# DriverModuleSkinny.net
KiCad netlist of a schematic drawn in EAGLE
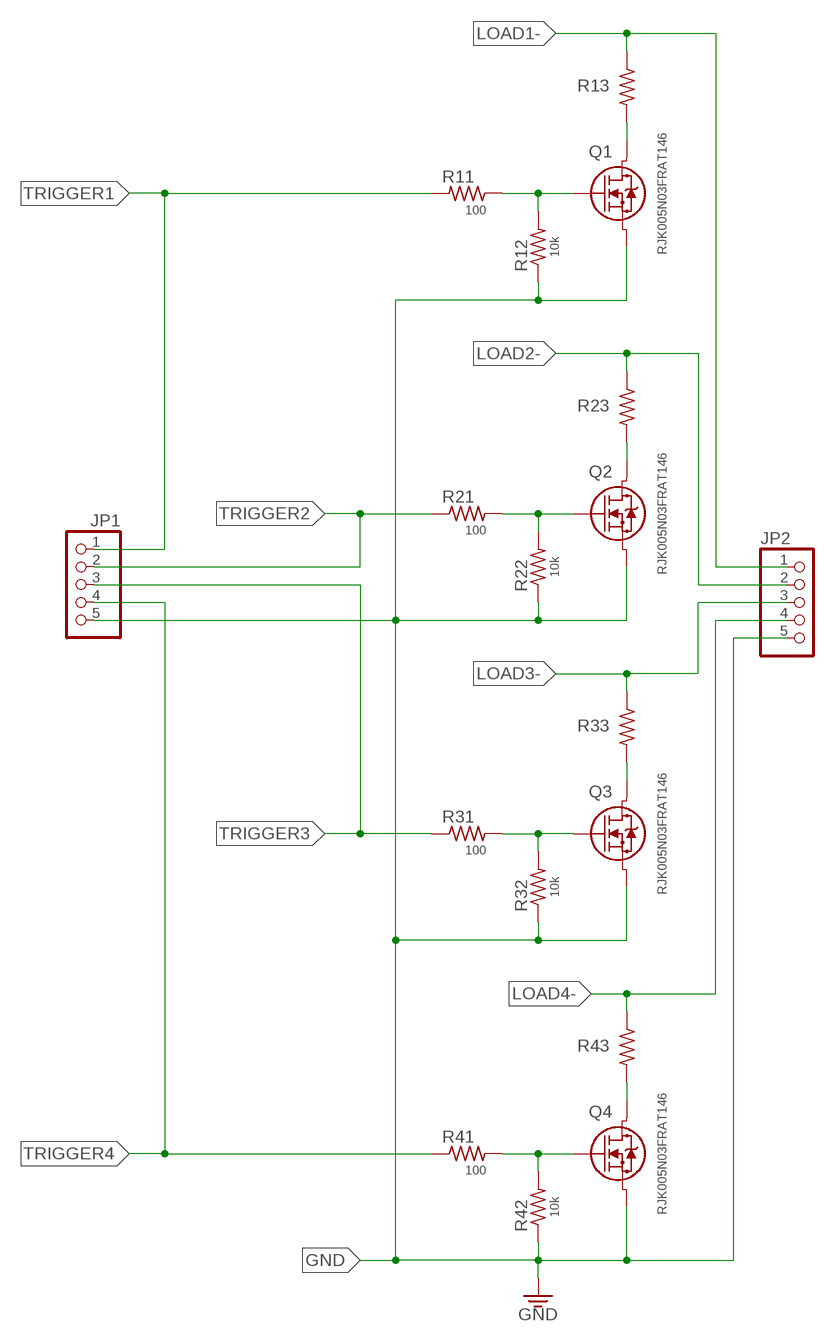
[diagram p0: schematic, sheet 1]

(export (version "E")
  (design (tool "Eeschema 10.0.6"))
  (components
    (comp (ref "JP1")
      (value "HEADER-1X576MIL")
      (footprint "eagle-import:1X05_ROUND_76")
      (libsource (lib "eagle-import") (part "HEADER-1X576MIL"))
    )
    (comp (ref "JP2")
      (value "HEADER-1X576MIL")
      (footprint "eagle-import:1X05_ROUND_76")
      (libsource (lib "eagle-import") (part "HEADER-1X576MIL"))
    )
    (comp (ref "Q1")
      (value "RJK005N03FRAT146")
      (footprint "eagle-import:TRANS_RHK003N_ROM-M")
      (fields (field (name "COPYRIGHT") "Copyright (C) 2022 Ultra Librarian. All rights reserved."))
      (libsource (lib "eagle-import") (part "RJK005N03FRAT146TRANS_RHK003N_ROM-M"))
    )
    (comp (ref "Q2")
      (value "RJK005N03FRAT146")
      (footprint "eagle-import:TRANS_RHK003N_ROM-M")
      (fields (field (name "COPYRIGHT") "Copyright (C) 2022 Ultra Librarian. All rights reserved."))
      (libsource (lib "eagle-import") (part "RJK005N03FRAT146TRANS_RHK003N_ROM-M"))
    )
    (comp (ref "Q3")
      (value "RJK005N03FRAT146")
      (footprint "eagle-import:TRANS_RHK003N_ROM-M")
      (fields (field (name "COPYRIGHT") "Copyright (C) 2022 Ultra Librarian. All rights reserved."))
      (libsource (lib "eagle-import") (part "RJK005N03FRAT146TRANS_RHK003N_ROM-M"))
    )
    (comp (ref "Q4")
      (value "RJK005N03FRAT146")
      (footprint "eagle-import:TRANS_RHK003N_ROM-M")
      (fields (field (name "COPYRIGHT") "Copyright (C) 2022 Ultra Librarian. All rights reserved."))
      (libsource (lib "eagle-import") (part "RJK005N03FRAT146TRANS_RHK003N_ROM-M"))
    )
    (comp (ref "R11")
      (value "100")
      (footprint "eagle-import:R0603")
      (libsource (lib "eagle-import") (part "R-US_R0603"))
    )
    (comp (ref "R12")
      (value "10k")
      (footprint "eagle-import:R0603")
      (libsource (lib "eagle-import") (part "R-US_R0603"))
    )
    (comp (ref "R13")
      (value "R-US_R1206")
      (footprint "eagle-import:R1206")
      (libsource (lib "eagle-import") (part "R-US_R1206"))
    )
    (comp (ref "R21")
      (value "100")
      (footprint "eagle-import:R0603")
      (libsource (lib "eagle-import") (part "R-US_R0603"))
    )
    (comp (ref "R22")
      (value "10k")
      (footprint "eagle-import:R0603")
      (libsource (lib "eagle-import") (part "R-US_R0603"))
    )
    (comp (ref "R23")
      (value "R-US_R1206")
      (footprint "eagle-import:R1206")
      (libsource (lib "eagle-import") (part "R-US_R1206"))
    )
    (comp (ref "R31")
      (value "100")
      (footprint "eagle-import:R0603")
      (libsource (lib "eagle-import") (part "R-US_R0603"))
    )
    (comp (ref "R32")
      (value "10k")
      (footprint "eagle-import:R0603")
      (libsource (lib "eagle-import") (part "R-US_R0603"))
    )
    (comp (ref "R33")
      (value "R-US_R1206")
      (footprint "eagle-import:R1206")
      (libsource (lib "eagle-import") (part "R-US_R1206"))
    )
    (comp (ref "R41")
      (value "100")
      (footprint "eagle-import:R0603")
      (libsource (lib "eagle-import") (part "R-US_R0603"))
    )
    (comp (ref "R42")
      (value "10k")
      (footprint "eagle-import:R0603")
      (libsource (lib "eagle-import") (part "R-US_R0603"))
    )
    (comp (ref "R43")
      (value "R-US_R1206")
      (footprint "eagle-import:R1206")
      (libsource (lib "eagle-import") (part "R-US_R1206"))
    )
  )
  (nets
    (net (code "1") (name "GND") (class "Default")
      (node (ref "JP1") (pin "5") (pinfunction "5_5") (pintype "passive"))
      (node (ref "JP2") (pin "5") (pinfunction "5_5") (pintype "passive"))
      (node (ref "Q1") (pin "3") (pinfunction "3_3") (pintype "passive"))
      (node (ref "Q2") (pin "3") (pinfunction "3_3") (pintype "passive"))
      (node (ref "Q3") (pin "3") (pinfunction "3_3") (pintype "passive"))
      (node (ref "Q4") (pin "3") (pinfunction "3_3") (pintype "passive"))
      (node (ref "R12") (pin "1") (pinfunction "1_1") (pintype "passive"))
      (node (ref "R22") (pin "1") (pinfunction "1_1") (pintype "passive"))
      (node (ref "R32") (pin "1") (pinfunction "1_1") (pintype "passive"))
      (node (ref "R42") (pin "1") (pinfunction "1_1") (pintype "passive"))
    )
    (net (code "2") (name "LOAD1-") (class "Default")
      (node (ref "JP2") (pin "1") (pinfunction "1_1") (pintype "passive"))
      (node (ref "R13") (pin "1") (pinfunction "1_1") (pintype "passive"))
    )
    (net (code "3") (name "LOAD2-") (class "Default")
      (node (ref "JP2") (pin "2") (pinfunction "2_2") (pintype "passive"))
      (node (ref "R23") (pin "1") (pinfunction "1_1") (pintype "passive"))
    )
    (net (code "4") (name "LOAD3-") (class "Default")
      (node (ref "JP2") (pin "3") (pinfunction "3_3") (pintype "passive"))
      (node (ref "R33") (pin "1") (pinfunction "1_1") (pintype "passive"))
    )
    (net (code "5") (name "LOAD4-") (class "Default")
      (node (ref "JP2") (pin "4") (pinfunction "4_4") (pintype "passive"))
      (node (ref "R43") (pin "1") (pinfunction "1_1") (pintype "passive"))
    )
    (net (code "6") (name "Net-(Q1-1)") (class "Default")
      (node (ref "Q1") (pin "2") (pinfunction "1_2") (pintype "passive"))
      (node (ref "R11") (pin "1") (pinfunction "1_1") (pintype "passive"))
      (node (ref "R12") (pin "2") (pinfunction "2_2") (pintype "passive"))
    )
    (net (code "7") (name "Net-(Q1-2)") (class "Default")
      (node (ref "Q1") (pin "1") (pinfunction "2_1") (pintype "passive"))
      (node (ref "R13") (pin "2") (pinfunction "2_2") (pintype "passive"))
    )
    (net (code "8") (name "Net-(Q2-1)") (class "Default")
      (node (ref "Q2") (pin "2") (pinfunction "1_2") (pintype "passive"))
      (node (ref "R21") (pin "2") (pinfunction "2_2") (pintype "passive"))
      (node (ref "R22") (pin "2") (pinfunction "2_2") (pintype "passive"))
    )
    (net (code "9") (name "Net-(Q2-2)") (class "Default")
      (node (ref "Q2") (pin "1") (pinfunction "2_1") (pintype "passive"))
      (node (ref "R23") (pin "2") (pinfunction "2_2") (pintype "passive"))
    )
    (net (code "10") (name "Net-(Q3-1)") (class "Default")
      (node (ref "Q3") (pin "2") (pinfunction "1_2") (pintype "passive"))
      (node (ref "R31") (pin "2") (pinfunction "2_2") (pintype "passive"))
      (node (ref "R32") (pin "2") (pinfunction "2_2") (pintype "passive"))
    )
    (net (code "11") (name "Net-(Q3-2)") (class "Default")
      (node (ref "Q3") (pin "1") (pinfunction "2_1") (pintype "passive"))
      (node (ref "R33") (pin "2") (pinfunction "2_2") (pintype "passive"))
    )
    (net (code "12") (name "Net-(Q4-1)") (class "Default")
      (node (ref "Q4") (pin "2") (pinfunction "1_2") (pintype "passive"))
      (node (ref "R41") (pin "2") (pinfunction "2_2") (pintype "passive"))
      (node (ref "R42") (pin "2") (pinfunction "2_2") (pintype "passive"))
    )
    (net (code "13") (name "Net-(Q4-2)") (class "Default")
      (node (ref "Q4") (pin "1") (pinfunction "2_1") (pintype "passive"))
      (node (ref "R43") (pin "2") (pinfunction "2_2") (pintype "passive"))
    )
    (net (code "14") (name "TRIGGER1") (class "Default")
      (node (ref "JP1") (pin "1") (pinfunction "1_1") (pintype "passive"))
      (node (ref "R11") (pin "2") (pinfunction "2_2") (pintype "passive"))
    )
    (net (code "15") (name "TRIGGER2") (class "Default")
      (node (ref "JP1") (pin "2") (pinfunction "2_2") (pintype "passive"))
      (node (ref "R21") (pin "1") (pinfunction "1_1") (pintype "passive"))
    )
    (net (code "16") (name "TRIGGER3") (class "Default")
      (node (ref "JP1") (pin "3") (pinfunction "3_3") (pintype "passive"))
      (node (ref "R31") (pin "1") (pinfunction "1_1") (pintype "passive"))
    )
    (net (code "17") (name "TRIGGER4") (class "Default")
      (node (ref "JP1") (pin "4") (pinfunction "4_4") (pintype "passive"))
      (node (ref "R41") (pin "1") (pinfunction "1_1") (pintype "passive"))
    )
  )
)
